# JTAG.net
KiCad netlist of a schematic drawn in Altium Designer
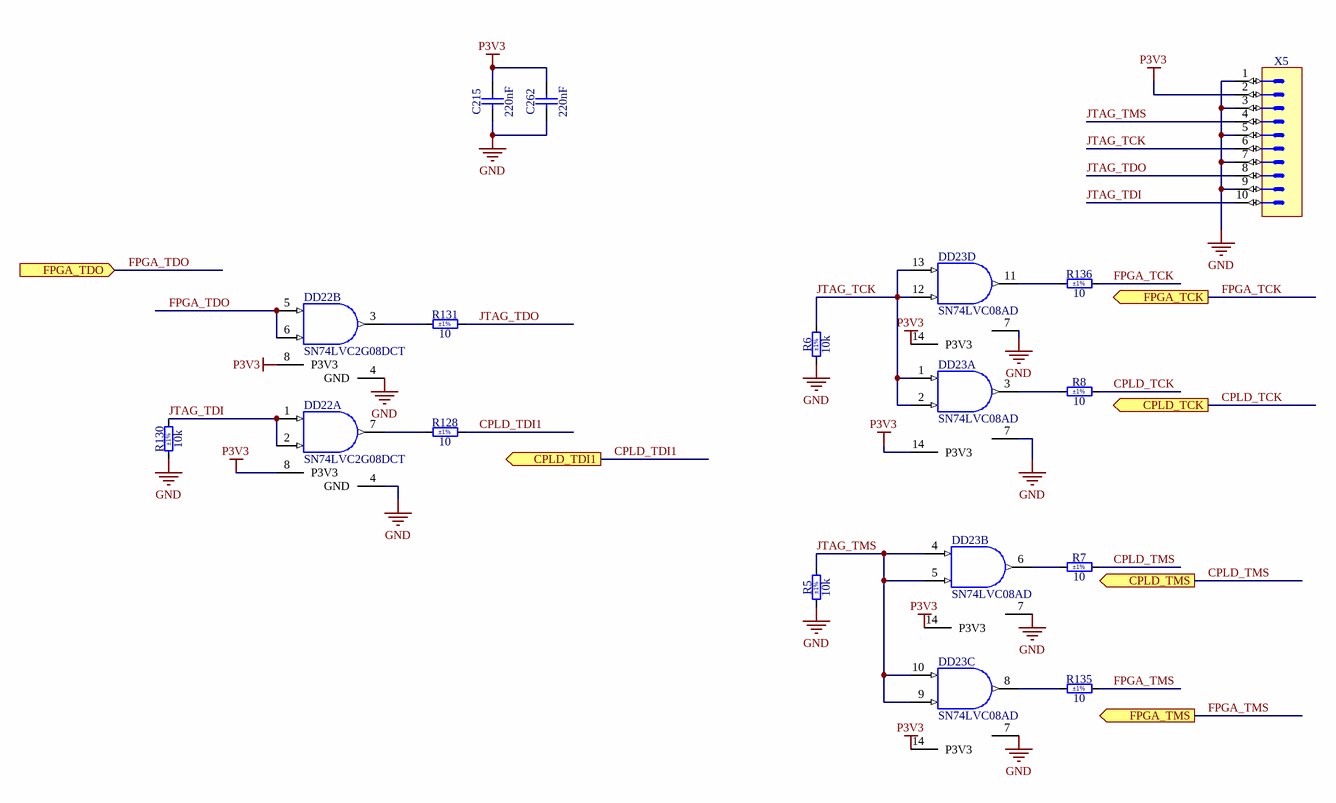
[diagram p0: JTAG.SchDoc]

(export (version "E")
  (design (tool "Eeschema 10.0.6"))
  (components
    (comp (ref "C215")
      (value "220nF")
      (footprint "CAPC2012X135N")
      (description "Non-polarised capacitor")
      (fields
        (field (name "PART NUMBER") "CC0805_220NF_50V_10%_X7R")
        (field (name "VOLTAGE") "50V")
        (field (name "AUTHOR") "CERN DEM JLC")
      )
      (libsource (lib "Capacitors") (part "Capacitor - non polarized"))
    )
    (comp (ref "C262")
      (value "220nF")
      (footprint "CAPC2012X135N")
      (description "Non-polarised capacitor")
      (fields
        (field (name "PART NUMBER") "CC0805_220NF_50V_10%_X7R")
        (field (name "VOLTAGE") "50V")
        (field (name "AUTHOR") "CERN DEM JLC")
      )
      (libsource (lib "Capacitors") (part "Capacitor - non polarized"))
    )
    (comp (ref "DD22")
      (value "SN74LVC2G08DCT")
      (footprint "SOP65P400X130-8N")
      (description "Dual 2-Input Positive AND Gate")
      (fields (field (name "MANUFACTURER") "TEXAS INSTRUMENTS") (field (name "AUTHOR") "CERN DEM MR"))
      (libsource (lib "ICs And Semiconductors") (part "742G08"))
    )
    (comp (ref "DD23")
      (value "SN74LVC08AD")
      (footprint "SOIC127P600X175-14N")
      (description "Quad 2-Input AND Gate")
      (fields (field (name "MANUFACTURER") "TEXAS INSTRUMENTS") (field (name "AUTHOR") "CERN DEM JLC"))
      (libsource (lib "ICs And Semiconductors") (part "7408"))
    )
    (comp (ref "R5")
      (value "10k")
      (footprint "RESC2012X60N")
      (description "Resistor - 1%")
      (fields
        (field (name "TOLERANCE") "±1%")
        (field (name "PART NUMBER") "R0805_10K_1%_0.125W_100PPM")
        (field (name "POWER") "0.125W")
        (field (name "AUTHOR") "CERN DEM JLC")
      )
      (libsource (lib "Resistors") (part "Resistor - 1%"))
    )
    (comp (ref "R6")
      (value "10k")
      (footprint "RESC2012X60N")
      (description "Resistor - 1%")
      (fields
        (field (name "TOLERANCE") "±1%")
        (field (name "PART NUMBER") "R0805_10K_1%_0.125W_100PPM")
        (field (name "POWER") "0.125W")
        (field (name "AUTHOR") "CERN DEM JLC")
      )
      (libsource (lib "Resistors") (part "Resistor - 1%"))
    )
    (comp (ref "R7")
      (value "10")
      (footprint "RESC2012X70N")
      (description "Resistor - 1%")
      (fields
        (field (name "TOLERANCE") "±1%")
        (field (name "PART NUMBER") "R0805_10R_1%_0.125W_100PPM_PANASONIC_ERJ")
        (field (name "POWER") "0.125W")
        (field (name "AUTHOR") "CERN DEM HF")
      )
      (libsource (lib "Resistors") (part "Resistor - 1%"))
    )
    (comp (ref "R8")
      (value "10")
      (footprint "RESC2012X70N")
      (description "Resistor - 1%")
      (fields
        (field (name "TOLERANCE") "±1%")
        (field (name "PART NUMBER") "R0805_10R_1%_0.125W_100PPM_PANASONIC_ERJ")
        (field (name "POWER") "0.125W")
        (field (name "AUTHOR") "CERN DEM HF")
      )
      (libsource (lib "Resistors") (part "Resistor - 1%"))
    )
    (comp (ref "R128")
      (value "10")
      (footprint "RESC2012X70N")
      (description "Resistor - 1%")
      (fields
        (field (name "TOLERANCE") "±1%")
        (field (name "PART NUMBER") "R0805_10R_1%_0.125W_100PPM_PANASONIC_ERJ")
        (field (name "POWER") "0.125W")
        (field (name "AUTHOR") "CERN DEM HF")
      )
      (libsource (lib "Resistors") (part "Resistor - 1%"))
    )
    (comp (ref "R130")
      (value "10k")
      (footprint "RESC2012X60N")
      (description "Resistor - 1%")
      (fields
        (field (name "TOLERANCE") "±1%")
        (field (name "PART NUMBER") "R0805_10K_1%_0.125W_100PPM")
        (field (name "POWER") "0.125W")
        (field (name "AUTHOR") "CERN DEM JLC")
      )
      (libsource (lib "Resistors") (part "Resistor - 1%"))
    )
    (comp (ref "R131")
      (value "10")
      (footprint "RESC2012X70N")
      (description "Resistor - 1%")
      (fields
        (field (name "TOLERANCE") "±1%")
        (field (name "PART NUMBER") "R0805_10R_1%_0.125W_100PPM_PANASONIC_ERJ")
        (field (name "POWER") "0.125W")
        (field (name "AUTHOR") "CERN DEM HF")
      )
      (libsource (lib "Resistors") (part "Resistor - 1%"))
    )
    (comp (ref "R135")
      (value "10")
      (footprint "RESC2012X70N")
      (description "Resistor - 1%")
      (fields
        (field (name "TOLERANCE") "±1%")
        (field (name "PART NUMBER") "R0805_10R_1%_0.125W_100PPM_PANASONIC_ERJ")
        (field (name "POWER") "0.125W")
        (field (name "AUTHOR") "CERN DEM HF")
      )
      (libsource (lib "Resistors") (part "Resistor - 1%"))
    )
    (comp (ref "R136")
      (value "10")
      (footprint "RESC2012X70N")
      (description "Resistor - 1%")
      (fields
        (field (name "TOLERANCE") "±1%")
        (field (name "PART NUMBER") "R0805_10R_1%_0.125W_100PPM_PANASONIC_ERJ")
        (field (name "POWER") "0.125W")
        (field (name "AUTHOR") "CERN DEM HF")
      )
      (libsource (lib "Resistors") (part "Resistor - 1%"))
    )
    (comp (ref "X5")
      (value "~")
      (footprint "CONNFLY_DS1014-10SF1B-B")
      (description "Connector 10 Male")
      (fields
        (field (name "PART NUMBER") "CONNFLY_DS1014-10SF1B-B")
        (field (name "MANUFACTURER") "CONNFLY")
        (field (name "AUTHOR") "CERN DEM HF")
      )
      (libsource (lib "Connectors") (part "Connector 10 Male"))
    )
  )
  (nets
    (net (code "1") (name "/CPLD_TCK") (class "Default")
      (node (ref "R8") (pin "2") (pinfunction "2_2") (pintype "passive"))
    )
    (net (code "2") (name "/CPLD_TDI1") (class "Default")
      (node (ref "R128") (pin "2") (pinfunction "2_2") (pintype "passive"))
    )
    (net (code "3") (name "/CPLD_TMS") (class "Default")
      (node (ref "R7") (pin "2") (pinfunction "2_2") (pintype "passive"))
    )
    (net (code "4") (name "/FPGA_TCK") (class "Default")
      (node (ref "R136") (pin "2") (pinfunction "2_2") (pintype "passive"))
    )
    (net (code "5") (name "/FPGA_TDO") (class "Default")
      (node (ref "DD22") (pin "5") (pinfunction "A_5") (pintype "input"))
      (node (ref "DD22") (pin "6") (pinfunction "B_6") (pintype "input"))
    )
    (net (code "6") (name "/FPGA_TMS") (class "Default")
      (node (ref "R135") (pin "2") (pinfunction "2_2") (pintype "passive"))
    )
    (net (code "7") (name "/JTAG_TCK") (class "Default")
      (node (ref "DD23") (pin "1") (pinfunction "A_1") (pintype "input"))
      (node (ref "DD23") (pin "12") (pinfunction "B_12") (pintype "input"))
      (node (ref "DD23") (pin "13") (pinfunction "A_13") (pintype "input"))
      (node (ref "DD23") (pin "2") (pinfunction "B_2") (pintype "input"))
      (node (ref "R6") (pin "2") (pinfunction "2_2") (pintype "passive"))
      (node (ref "X5") (pin "6") (pinfunction "6_6") (pintype "bidirectional"))
    )
    (net (code "8") (name "/JTAG_TDI") (class "Default")
      (node (ref "DD22") (pin "1") (pinfunction "A_1") (pintype "input"))
      (node (ref "DD22") (pin "2") (pinfunction "B_2") (pintype "input"))
      (node (ref "R130") (pin "2") (pinfunction "2_2") (pintype "passive"))
      (node (ref "X5") (pin "10") (pinfunction "10_10") (pintype "bidirectional"))
    )
    (net (code "9") (name "/JTAG_TDO") (class "Default")
      (node (ref "R131") (pin "2") (pinfunction "2_2") (pintype "passive"))
      (node (ref "X5") (pin "8") (pinfunction "8_8") (pintype "bidirectional"))
    )
    (net (code "10") (name "/JTAG_TMS") (class "Default")
      (node (ref "DD23") (pin "10") (pinfunction "A_10") (pintype "input"))
      (node (ref "DD23") (pin "4") (pinfunction "A_4") (pintype "input"))
      (node (ref "DD23") (pin "5") (pinfunction "B_5") (pintype "input"))
      (node (ref "DD23") (pin "9") (pinfunction "B_9") (pintype "input"))
      (node (ref "R5") (pin "2") (pinfunction "2_2") (pintype "passive"))
      (node (ref "X5") (pin "4") (pinfunction "4_4") (pintype "bidirectional"))
    )
    (net (code "11") (name "GND") (class "Default")
      (node (ref "C215") (pin "1") (pinfunction "1_1") (pintype "passive"))
      (node (ref "C262") (pin "1") (pinfunction "1_1") (pintype "passive"))
      (node (ref "DD22") (pin "4") (pinfunction "GND_4") (pintype "power_in"))
      (node (ref "DD23") (pin "7") (pinfunction "GND_7") (pintype "power_in"))
      (node (ref "R130") (pin "1") (pinfunction "1_1") (pintype "passive"))
      (node (ref "R5") (pin "1") (pinfunction "1_1") (pintype "passive"))
      (node (ref "R6") (pin "1") (pinfunction "1_1") (pintype "passive"))
      (node (ref "X5") (pin "1") (pinfunction "1_1") (pintype "bidirectional"))
      (node (ref "X5") (pin "3") (pinfunction "3_3") (pintype "bidirectional"))
      (node (ref "X5") (pin "5") (pinfunction "5_5") (pintype "bidirectional"))
      (node (ref "X5") (pin "7") (pinfunction "7_7") (pintype "bidirectional"))
      (node (ref "X5") (pin "9") (pinfunction "9_9") (pintype "bidirectional"))
    )
    (net (code "12") (name "Net-(DD22A-Y)") (class "Default")
      (node (ref "DD22") (pin "7") (pinfunction "Y_7") (pintype "output"))
      (node (ref "R128") (pin "1") (pinfunction "1_1") (pintype "passive"))
    )
    (net (code "13") (name "Net-(DD22B-Y)") (class "Default")
      (node (ref "DD22") (pin "3") (pinfunction "Y_3") (pintype "output"))
      (node (ref "R131") (pin "1") (pinfunction "1_1") (pintype "passive"))
    )
    (net (code "14") (name "Net-(DD23A-Y)") (class "Default")
      (node (ref "DD23") (pin "3") (pinfunction "Y_3") (pintype "output"))
      (node (ref "R8") (pin "1") (pinfunction "1_1") (pintype "passive"))
    )
    (net (code "15") (name "Net-(DD23B-Y)") (class "Default")
      (node (ref "DD23") (pin "6") (pinfunction "Y_6") (pintype "output"))
      (node (ref "R7") (pin "1") (pinfunction "1_1") (pintype "passive"))
    )
    (net (code "16") (name "Net-(DD23C-Y)") (class "Default")
      (node (ref "DD23") (pin "8") (pinfunction "Y_8") (pintype "output"))
      (node (ref "R135") (pin "1") (pinfunction "1_1") (pintype "passive"))
    )
    (net (code "17") (name "Net-(DD23D-Y)") (class "Default")
      (node (ref "DD23") (pin "11") (pinfunction "Y_11") (pintype "output"))
      (node (ref "R136") (pin "1") (pinfunction "1_1") (pintype "passive"))
    )
    (net (code "18") (name "P3V3") (class "Default")
      (node (ref "C215") (pin "2") (pinfunction "2_2") (pintype "passive"))
      (node (ref "C262") (pin "2") (pinfunction "2_2") (pintype "passive"))
      (node (ref "DD22") (pin "8") (pinfunction "P3V3_8") (pintype "power_in"))
      (node (ref "DD23") (pin "14") (pinfunction "P3V3_14") (pintype "power_in"))
      (node (ref "X5") (pin "2") (pinfunction "2_2") (pintype "bidirectional"))
    )
  )
)
